# BottomSide.net
KiCad netlist of a schematic drawn in Altium Designer
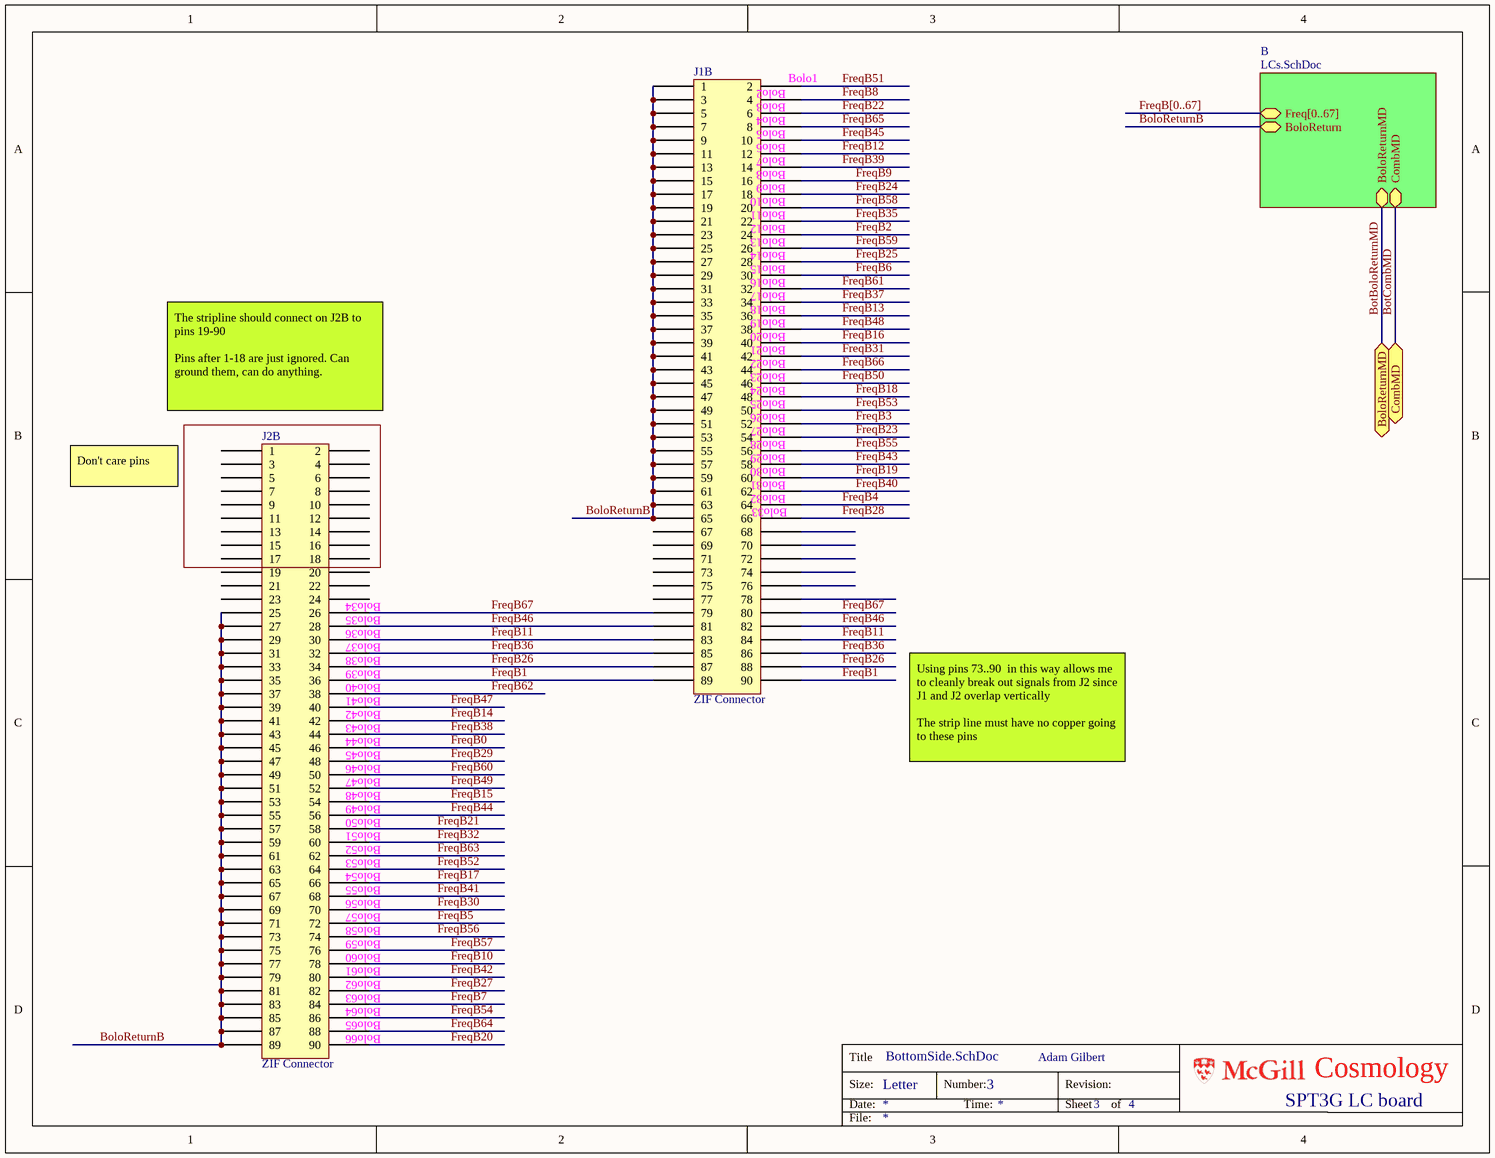
[diagram p0: BottomSide.SchDoc]

(export (version "E")
  (design (tool "Eeschema 10.0.6"))
  (components
    (comp (ref "J1B")
      (value "ZIF Connector")
      (footprint "LCBoard_ZIFCon")
      (libsource (lib "SPT3G_LCBoard") (part "LCboard_FH16-90S-0.3SHW(05)"))
    )
    (comp (ref "J2B")
      (value "ZIF Connector")
      (footprint "LCBoard_ZIFCon")
      (libsource (lib "SPT3G_LCBoard") (part "LCboard_FH16-90S-0.3SHW(05)"))
    )
  )
  (nets
    (net (code "3") (name "/BoloReturnB") (class "Default")
      (node (ref "J1B") (pin "1") (pinfunction "1_1") (pintype "passive"))
      (node (ref "J1B") (pin "11") (pinfunction "11_11") (pintype "passive"))
      (node (ref "J1B") (pin "13") (pinfunction "13_13") (pintype "passive"))
      (node (ref "J1B") (pin "15") (pinfunction "15_15") (pintype "passive"))
      (node (ref "J1B") (pin "17") (pinfunction "17_17") (pintype "passive"))
      (node (ref "J1B") (pin "19") (pinfunction "19_19") (pintype "passive"))
      (node (ref "J1B") (pin "21") (pinfunction "21_21") (pintype "passive"))
      (node (ref "J1B") (pin "23") (pinfunction "23_23") (pintype "passive"))
      (node (ref "J1B") (pin "25") (pinfunction "25_25") (pintype "passive"))
      (node (ref "J1B") (pin "27") (pinfunction "27_27") (pintype "passive"))
      (node (ref "J1B") (pin "29") (pinfunction "29_29") (pintype "passive"))
      (node (ref "J1B") (pin "3") (pinfunction "3_3") (pintype "passive"))
      (node (ref "J1B") (pin "31") (pinfunction "31_31") (pintype "passive"))
      (node (ref "J1B") (pin "33") (pinfunction "33_33") (pintype "passive"))
      (node (ref "J1B") (pin "35") (pinfunction "35_35") (pintype "passive"))
      (node (ref "J1B") (pin "37") (pinfunction "37_37") (pintype "passive"))
      (node (ref "J1B") (pin "39") (pinfunction "39_39") (pintype "passive"))
      (node (ref "J1B") (pin "41") (pinfunction "41_41") (pintype "passive"))
      (node (ref "J1B") (pin "43") (pinfunction "43_43") (pintype "passive"))
      (node (ref "J1B") (pin "45") (pinfunction "45_45") (pintype "passive"))
      (node (ref "J1B") (pin "47") (pinfunction "47_47") (pintype "passive"))
      (node (ref "J1B") (pin "49") (pinfunction "49_49") (pintype "passive"))
      (node (ref "J1B") (pin "5") (pinfunction "5_5") (pintype "passive"))
      (node (ref "J1B") (pin "51") (pinfunction "51_51") (pintype "passive"))
      (node (ref "J1B") (pin "53") (pinfunction "53_53") (pintype "passive"))
      (node (ref "J1B") (pin "55") (pinfunction "55_55") (pintype "passive"))
      (node (ref "J1B") (pin "57") (pinfunction "57_57") (pintype "passive"))
      (node (ref "J1B") (pin "59") (pinfunction "59_59") (pintype "passive"))
      (node (ref "J1B") (pin "61") (pinfunction "61_61") (pintype "passive"))
      (node (ref "J1B") (pin "63") (pinfunction "63_63") (pintype "passive"))
      (node (ref "J1B") (pin "65") (pinfunction "65_65") (pintype "passive"))
      (node (ref "J1B") (pin "7") (pinfunction "7_7") (pintype "passive"))
      (node (ref "J1B") (pin "9") (pinfunction "9_9") (pintype "passive"))
      (node (ref "J2B") (pin "25") (pinfunction "25_25") (pintype "passive"))
      (node (ref "J2B") (pin "27") (pinfunction "27_27") (pintype "passive"))
      (node (ref "J2B") (pin "29") (pinfunction "29_29") (pintype "passive"))
      (node (ref "J2B") (pin "31") (pinfunction "31_31") (pintype "passive"))
      (node (ref "J2B") (pin "33") (pinfunction "33_33") (pintype "passive"))
      (node (ref "J2B") (pin "35") (pinfunction "35_35") (pintype "passive"))
      (node (ref "J2B") (pin "37") (pinfunction "37_37") (pintype "passive"))
      (node (ref "J2B") (pin "39") (pinfunction "39_39") (pintype "passive"))
      (node (ref "J2B") (pin "41") (pinfunction "41_41") (pintype "passive"))
      (node (ref "J2B") (pin "43") (pinfunction "43_43") (pintype "passive"))
      (node (ref "J2B") (pin "45") (pinfunction "45_45") (pintype "passive"))
      (node (ref "J2B") (pin "47") (pinfunction "47_47") (pintype "passive"))
      (node (ref "J2B") (pin "49") (pinfunction "49_49") (pintype "passive"))
      (node (ref "J2B") (pin "51") (pinfunction "51_51") (pintype "passive"))
      (node (ref "J2B") (pin "53") (pinfunction "53_53") (pintype "passive"))
      (node (ref "J2B") (pin "55") (pinfunction "55_55") (pintype "passive"))
      (node (ref "J2B") (pin "57") (pinfunction "57_57") (pintype "passive"))
      (node (ref "J2B") (pin "59") (pinfunction "59_59") (pintype "passive"))
      (node (ref "J2B") (pin "61") (pinfunction "61_61") (pintype "passive"))
      (node (ref "J2B") (pin "63") (pinfunction "63_63") (pintype "passive"))
      (node (ref "J2B") (pin "65") (pinfunction "65_65") (pintype "passive"))
      (node (ref "J2B") (pin "67") (pinfunction "67_67") (pintype "passive"))
      (node (ref "J2B") (pin "69") (pinfunction "69_69") (pintype "passive"))
      (node (ref "J2B") (pin "71") (pinfunction "71_71") (pintype "passive"))
      (node (ref "J2B") (pin "73") (pinfunction "73_73") (pintype "passive"))
      (node (ref "J2B") (pin "75") (pinfunction "75_75") (pintype "passive"))
      (node (ref "J2B") (pin "77") (pinfunction "77_77") (pintype "passive"))
      (node (ref "J2B") (pin "79") (pinfunction "79_79") (pintype "passive"))
      (node (ref "J2B") (pin "81") (pinfunction "81_81") (pintype "passive"))
      (node (ref "J2B") (pin "83") (pinfunction "83_83") (pintype "passive"))
      (node (ref "J2B") (pin "85") (pinfunction "85_85") (pintype "passive"))
      (node (ref "J2B") (pin "87") (pinfunction "87_87") (pintype "passive"))
      (node (ref "J2B") (pin "89") (pinfunction "89_89") (pintype "passive"))
    )
    (net (code "6") (name "/FreqB0") (class "Default")
      (node (ref "J2B") (pin "46") (pinfunction "46_46") (pintype "passive"))
    )
    (net (code "7") (name "/FreqB1") (class "Default")
      (node (ref "J1B") (pin "89") (pinfunction "89_89") (pintype "passive"))
      (node (ref "J1B") (pin "90") (pinfunction "90_90") (pintype "passive"))
      (node (ref "J2B") (pin "36") (pinfunction "36_36") (pintype "passive"))
    )
    (net (code "8") (name "/FreqB2") (class "Default")
      (node (ref "J1B") (pin "24") (pinfunction "24_24") (pintype "passive"))
    )
    (net (code "9") (name "/FreqB3") (class "Default")
      (node (ref "J1B") (pin "52") (pinfunction "52_52") (pintype "passive"))
    )
    (net (code "10") (name "/FreqB4") (class "Default")
      (node (ref "J1B") (pin "64") (pinfunction "64_64") (pintype "passive"))
    )
    (net (code "11") (name "/FreqB5") (class "Default")
      (node (ref "J2B") (pin "72") (pinfunction "72_72") (pintype "passive"))
    )
    (net (code "12") (name "/FreqB6") (class "Default")
      (node (ref "J1B") (pin "30") (pinfunction "30_30") (pintype "passive"))
    )
    (net (code "13") (name "/FreqB7") (class "Default")
      (node (ref "J2B") (pin "84") (pinfunction "84_84") (pintype "passive"))
    )
    (net (code "14") (name "/FreqB8") (class "Default")
      (node (ref "J1B") (pin "4") (pinfunction "4_4") (pintype "passive"))
    )
    (net (code "15") (name "/FreqB9") (class "Default")
      (node (ref "J1B") (pin "16") (pinfunction "16_16") (pintype "passive"))
    )
    (net (code "16") (name "/FreqB10") (class "Default")
      (node (ref "J2B") (pin "78") (pinfunction "78_78") (pintype "passive"))
    )
    (net (code "17") (name "/FreqB11") (class "Default")
      (node (ref "J1B") (pin "83") (pinfunction "83_83") (pintype "passive"))
      (node (ref "J1B") (pin "84") (pinfunction "84_84") (pintype "passive"))
      (node (ref "J2B") (pin "30") (pinfunction "30_30") (pintype "passive"))
    )
    (net (code "18") (name "/FreqB12") (class "Default")
      (node (ref "J1B") (pin "12") (pinfunction "12_12") (pintype "passive"))
    )
    (net (code "19") (name "/FreqB13") (class "Default")
      (node (ref "J1B") (pin "36") (pinfunction "36_36") (pintype "passive"))
    )
    (net (code "20") (name "/FreqB14") (class "Default")
      (node (ref "J2B") (pin "42") (pinfunction "42_42") (pintype "passive"))
    )
    (net (code "21") (name "/FreqB15") (class "Default")
      (node (ref "J2B") (pin "54") (pinfunction "54_54") (pintype "passive"))
    )
    (net (code "22") (name "/FreqB16") (class "Default")
      (node (ref "J1B") (pin "40") (pinfunction "40_40") (pintype "passive"))
    )
    (net (code "23") (name "/FreqB17") (class "Default")
      (node (ref "J2B") (pin "66") (pinfunction "66_66") (pintype "passive"))
    )
    (net (code "24") (name "/FreqB18") (class "Default")
      (node (ref "J1B") (pin "48") (pinfunction "48_48") (pintype "passive"))
    )
    (net (code "25") (name "/FreqB19") (class "Default")
      (node (ref "J1B") (pin "60") (pinfunction "60_60") (pintype "passive"))
    )
    (net (code "26") (name "/FreqB20") (class "Default")
      (node (ref "J2B") (pin "90") (pinfunction "90_90") (pintype "passive"))
    )
    (net (code "27") (name "/FreqB21") (class "Default")
      (node (ref "J2B") (pin "58") (pinfunction "58_58") (pintype "passive"))
    )
    (net (code "28") (name "/FreqB22") (class "Default")
      (node (ref "J1B") (pin "6") (pinfunction "6_6") (pintype "passive"))
    )
    (net (code "29") (name "/FreqB23") (class "Default")
      (node (ref "J1B") (pin "54") (pinfunction "54_54") (pintype "passive"))
    )
    (net (code "30") (name "/FreqB24") (class "Default")
      (node (ref "J1B") (pin "18") (pinfunction "18_18") (pintype "passive"))
    )
    (net (code "31") (name "/FreqB25") (class "Default")
      (node (ref "J1B") (pin "28") (pinfunction "28_28") (pintype "passive"))
    )
    (net (code "32") (name "/FreqB26") (class "Default")
      (node (ref "J1B") (pin "87") (pinfunction "87_87") (pintype "passive"))
      (node (ref "J1B") (pin "88") (pinfunction "88_88") (pintype "passive"))
      (node (ref "J2B") (pin "34") (pinfunction "34_34") (pintype "passive"))
    )
    (net (code "33") (name "/FreqB27") (class "Default")
      (node (ref "J2B") (pin "82") (pinfunction "82_82") (pintype "passive"))
    )
    (net (code "34") (name "/FreqB28") (class "Default")
      (node (ref "J1B") (pin "66") (pinfunction "66_66") (pintype "passive"))
    )
    (net (code "35") (name "/FreqB29") (class "Default")
      (node (ref "J2B") (pin "48") (pinfunction "48_48") (pintype "passive"))
    )
    (net (code "36") (name "/FreqB30") (class "Default")
      (node (ref "J2B") (pin "70") (pinfunction "70_70") (pintype "passive"))
    )
    (net (code "37") (name "/FreqB31") (class "Default")
      (node (ref "J1B") (pin "42") (pinfunction "42_42") (pintype "passive"))
    )
    (net (code "38") (name "/FreqB32") (class "Default")
      (node (ref "J2B") (pin "60") (pinfunction "60_60") (pintype "passive"))
    )
    (net (code "39") (name "/FreqB35") (class "Default")
      (node (ref "J1B") (pin "22") (pinfunction "22_22") (pintype "passive"))
    )
    (net (code "40") (name "/FreqB36") (class "Default")
      (node (ref "J1B") (pin "85") (pinfunction "85_85") (pintype "passive"))
      (node (ref "J1B") (pin "86") (pinfunction "86_86") (pintype "passive"))
      (node (ref "J2B") (pin "32") (pinfunction "32_32") (pintype "passive"))
    )
    (net (code "41") (name "/FreqB37") (class "Default")
      (node (ref "J1B") (pin "34") (pinfunction "34_34") (pintype "passive"))
    )
    (net (code "42") (name "/FreqB38") (class "Default")
      (node (ref "J2B") (pin "44") (pinfunction "44_44") (pintype "passive"))
    )
    (net (code "43") (name "/FreqB39") (class "Default")
      (node (ref "J1B") (pin "14") (pinfunction "14_14") (pintype "passive"))
    )
    (net (code "44") (name "/FreqB40") (class "Default")
      (node (ref "J1B") (pin "62") (pinfunction "62_62") (pintype "passive"))
    )
    (net (code "45") (name "/FreqB41") (class "Default")
      (node (ref "J2B") (pin "68") (pinfunction "68_68") (pintype "passive"))
    )
    (net (code "46") (name "/FreqB42") (class "Default")
      (node (ref "J2B") (pin "80") (pinfunction "80_80") (pintype "passive"))
    )
    (net (code "47") (name "/FreqB43") (class "Default")
      (node (ref "J1B") (pin "58") (pinfunction "58_58") (pintype "passive"))
    )
    (net (code "48") (name "/FreqB44") (class "Default")
      (node (ref "J2B") (pin "56") (pinfunction "56_56") (pintype "passive"))
    )
    (net (code "49") (name "/FreqB45") (class "Default")
      (node (ref "J1B") (pin "10") (pinfunction "10_10") (pintype "passive"))
    )
    (net (code "50") (name "/FreqB46") (class "Default")
      (node (ref "J1B") (pin "81") (pinfunction "81_81") (pintype "passive"))
      (node (ref "J1B") (pin "82") (pinfunction "82_82") (pintype "passive"))
      (node (ref "J2B") (pin "28") (pinfunction "28_28") (pintype "passive"))
    )
    (net (code "51") (name "/FreqB47") (class "Default")
      (node (ref "J2B") (pin "40") (pinfunction "40_40") (pintype "passive"))
    )
    (net (code "52") (name "/FreqB48") (class "Default")
      (node (ref "J1B") (pin "38") (pinfunction "38_38") (pintype "passive"))
    )
    (net (code "53") (name "/FreqB49") (class "Default")
      (node (ref "J2B") (pin "52") (pinfunction "52_52") (pintype "passive"))
    )
    (net (code "54") (name "/FreqB50") (class "Default")
      (node (ref "J1B") (pin "46") (pinfunction "46_46") (pintype "passive"))
    )
    (net (code "55") (name "/FreqB51") (class "Default")
      (node (ref "J1B") (pin "2") (pinfunction "2_2") (pintype "passive"))
    )
    (net (code "56") (name "/FreqB52") (class "Default")
      (node (ref "J2B") (pin "64") (pinfunction "64_64") (pintype "passive"))
    )
    (net (code "57") (name "/FreqB53") (class "Default")
      (node (ref "J1B") (pin "50") (pinfunction "50_50") (pintype "passive"))
    )
    (net (code "58") (name "/FreqB54") (class "Default")
      (node (ref "J2B") (pin "86") (pinfunction "86_86") (pintype "passive"))
    )
    (net (code "59") (name "/FreqB55") (class "Default")
      (node (ref "J1B") (pin "56") (pinfunction "56_56") (pintype "passive"))
    )
    (net (code "60") (name "/FreqB56") (class "Default")
      (node (ref "J2B") (pin "74") (pinfunction "74_74") (pintype "passive"))
    )
    (net (code "61") (name "/FreqB57") (class "Default")
      (node (ref "J2B") (pin "76") (pinfunction "76_76") (pintype "passive"))
    )
    (net (code "62") (name "/FreqB58") (class "Default")
      (node (ref "J1B") (pin "20") (pinfunction "20_20") (pintype "passive"))
    )
    (net (code "63") (name "/FreqB59") (class "Default")
      (node (ref "J1B") (pin "26") (pinfunction "26_26") (pintype "passive"))
    )
    (net (code "64") (name "/FreqB60") (class "Default")
      (node (ref "J2B") (pin "50") (pinfunction "50_50") (pintype "passive"))
    )
    (net (code "65") (name "/FreqB61") (class "Default")
      (node (ref "J1B") (pin "32") (pinfunction "32_32") (pintype "passive"))
    )
    (net (code "66") (name "/FreqB62") (class "Default")
      (node (ref "J2B") (pin "38") (pinfunction "38_38") (pintype "passive"))
    )
    (net (code "67") (name "/FreqB63") (class "Default")
      (node (ref "J2B") (pin "62") (pinfunction "62_62") (pintype "passive"))
    )
    (net (code "68") (name "/FreqB64") (class "Default")
      (node (ref "J2B") (pin "88") (pinfunction "88_88") (pintype "passive"))
    )
    (net (code "69") (name "/FreqB65") (class "Default")
      (node (ref "J1B") (pin "8") (pinfunction "8_8") (pintype "passive"))
    )
    (net (code "70") (name "/FreqB66") (class "Default")
      (node (ref "J1B") (pin "44") (pinfunction "44_44") (pintype "passive"))
    )
    (net (code "71") (name "/FreqB67") (class "Default")
      (node (ref "J1B") (pin "79") (pinfunction "79_79") (pintype "passive"))
      (node (ref "J1B") (pin "80") (pinfunction "80_80") (pintype "passive"))
      (node (ref "J2B") (pin "26") (pinfunction "26_26") (pintype "passive"))
    )
    (net (code "73") (name "unconnected-(J1B-Pad67)") (class "Default")
      (node (ref "J1B") (pin "67") (pinfunction "67_67") (pintype "passive"))
    )
    (net (code "74") (name "unconnected-(J1B-Pad68)") (class "Default")
      (node (ref "J1B") (pin "68") (pinfunction "68_68") (pintype "passive"))
    )
    (net (code "75") (name "unconnected-(J1B-Pad69)") (class "Default")
      (node (ref "J1B") (pin "69") (pinfunction "69_69") (pintype "passive"))
    )
    (net (code "76") (name "unconnected-(J1B-Pad70)") (class "Default")
      (node (ref "J1B") (pin "70") (pinfunction "70_70") (pintype "passive"))
    )
    (net (code "77") (name "unconnected-(J1B-Pad71)") (class "Default")
      (node (ref "J1B") (pin "71") (pinfunction "71_71") (pintype "passive"))
    )
    (net (code "78") (name "unconnected-(J1B-Pad72)") (class "Default")
      (node (ref "J1B") (pin "72") (pinfunction "72_72") (pintype "passive"))
    )
    (net (code "79") (name "unconnected-(J1B-Pad73)") (class "Default")
      (node (ref "J1B") (pin "73") (pinfunction "73_73") (pintype "passive"))
    )
    (net (code "80") (name "unconnected-(J1B-Pad74)") (class "Default")
      (node (ref "J1B") (pin "74") (pinfunction "74_74") (pintype "passive"))
    )
    (net (code "81") (name "unconnected-(J1B-Pad75)") (class "Default")
      (node (ref "J1B") (pin "75") (pinfunction "75_75") (pintype "passive"))
    )
    (net (code "82") (name "unconnected-(J1B-Pad76)") (class "Default")
      (node (ref "J1B") (pin "76") (pinfunction "76_76") (pintype "passive"))
    )
    (net (code "83") (name "unconnected-(J1B-Pad77)") (class "Default")
      (node (ref "J1B") (pin "77") (pinfunction "77_77") (pintype "passive"))
    )
    (net (code "84") (name "unconnected-(J1B-Pad78)") (class "Default")
      (node (ref "J1B") (pin "78") (pinfunction "78_78") (pintype "passive"))
    )
    (net (code "85") (name "unconnected-(J2B-Pad1)") (class "Default")
      (node (ref "J2B") (pin "1") (pinfunction "1_1") (pintype "passive"))
    )
    (net (code "86") (name "unconnected-(J2B-Pad2)") (class "Default")
      (node (ref "J2B") (pin "2") (pinfunction "2_2") (pintype "passive"))
    )
    (net (code "87") (name "unconnected-(J2B-Pad3)") (class "Default")
      (node (ref "J2B") (pin "3") (pinfunction "3_3") (pintype "passive"))
    )
    (net (code "88") (name "unconnected-(J2B-Pad4)") (class "Default")
      (node (ref "J2B") (pin "4") (pinfunction "4_4") (pintype "passive"))
    )
    (net (code "89") (name "unconnected-(J2B-Pad5)") (class "Default")
      (node (ref "J2B") (pin "5") (pinfunction "5_5") (pintype "passive"))
    )
    (net (code "90") (name "unconnected-(J2B-Pad6)") (class "Default")
      (node (ref "J2B") (pin "6") (pinfunction "6_6") (pintype "passive"))
    )
    (net (code "91") (name "unconnected-(J2B-Pad7)") (class "Default")
      (node (ref "J2B") (pin "7") (pinfunction "7_7") (pintype "passive"))
    )
    (net (code "92") (name "unconnected-(J2B-Pad8)") (class "Default")
      (node (ref "J2B") (pin "8") (pinfunction "8_8") (pintype "passive"))
    )
    (net (code "93") (name "unconnected-(J2B-Pad9)") (class "Default")
      (node (ref "J2B") (pin "9") (pinfunction "9_9") (pintype "passive"))
    )
    (net (code "94") (name "unconnected-(J2B-Pad10)") (class "Default")
      (node (ref "J2B") (pin "10") (pinfunction "10_10") (pintype "passive"))
    )
    (net (code "95") (name "unconnected-(J2B-Pad11)") (class "Default")
      (node (ref "J2B") (pin "11") (pinfunction "11_11") (pintype "passive"))
    )
    (net (code "96") (name "unconnected-(J2B-Pad12)") (class "Default")
      (node (ref "J2B") (pin "12") (pinfunction "12_12") (pintype "passive"))
    )
    (net (code "97") (name "unconnected-(J2B-Pad13)") (class "Default")
      (node (ref "J2B") (pin "13") (pinfunction "13_13") (pintype "passive"))
    )
    (net (code "98") (name "unconnected-(J2B-Pad14)") (class "Default")
      (node (ref "J2B") (pin "14") (pinfunction "14_14") (pintype "passive"))
    )
    (net (code "99") (name "unconnected-(J2B-Pad15)") (class "Default")
      (node (ref "J2B") (pin "15") (pinfunction "15_15") (pintype "passive"))
    )
    (net (code "100") (name "unconnected-(J2B-Pad16)") (class "Default")
      (node (ref "J2B") (pin "16") (pinfunction "16_16") (pintype "passive"))
    )
    (net (code "101") (name "unconnected-(J2B-Pad17)") (class "Default")
      (node (ref "J2B") (pin "17") (pinfunction "17_17") (pintype "passive"))
    )
    (net (code "102") (name "unconnected-(J2B-Pad18)") (class "Default")
      (node (ref "J2B") (pin "18") (pinfunction "18_18") (pintype "passive"))
    )
    (net (code "103") (name "unconnected-(J2B-Pad19)") (class "Default")
      (node (ref "J2B") (pin "19") (pinfunction "19_19") (pintype "passive"))
    )
    (net (code "104") (name "unconnected-(J2B-Pad20)") (class "Default")
      (node (ref "J2B") (pin "20") (pinfunction "20_20") (pintype "passive"))
    )
    (net (code "105") (name "unconnected-(J2B-Pad21)") (class "Default")
      (node (ref "J2B") (pin "21") (pinfunction "21_21") (pintype "passive"))
    )
    (net (code "106") (name "unconnected-(J2B-Pad22)") (class "Default")
      (node (ref "J2B") (pin "22") (pinfunction "22_22") (pintype "passive"))
    )
    (net (code "107") (name "unconnected-(J2B-Pad23)") (class "Default")
      (node (ref "J2B") (pin "23") (pinfunction "23_23") (pintype "passive"))
    )
    (net (code "108") (name "unconnected-(J2B-Pad24)") (class "Default")
      (node (ref "J2B") (pin "24") (pinfunction "24_24") (pintype "passive"))
    )
  )
)
